# AutoFeatherPower3.net
KiCad netlist of a schematic drawn in EAGLE
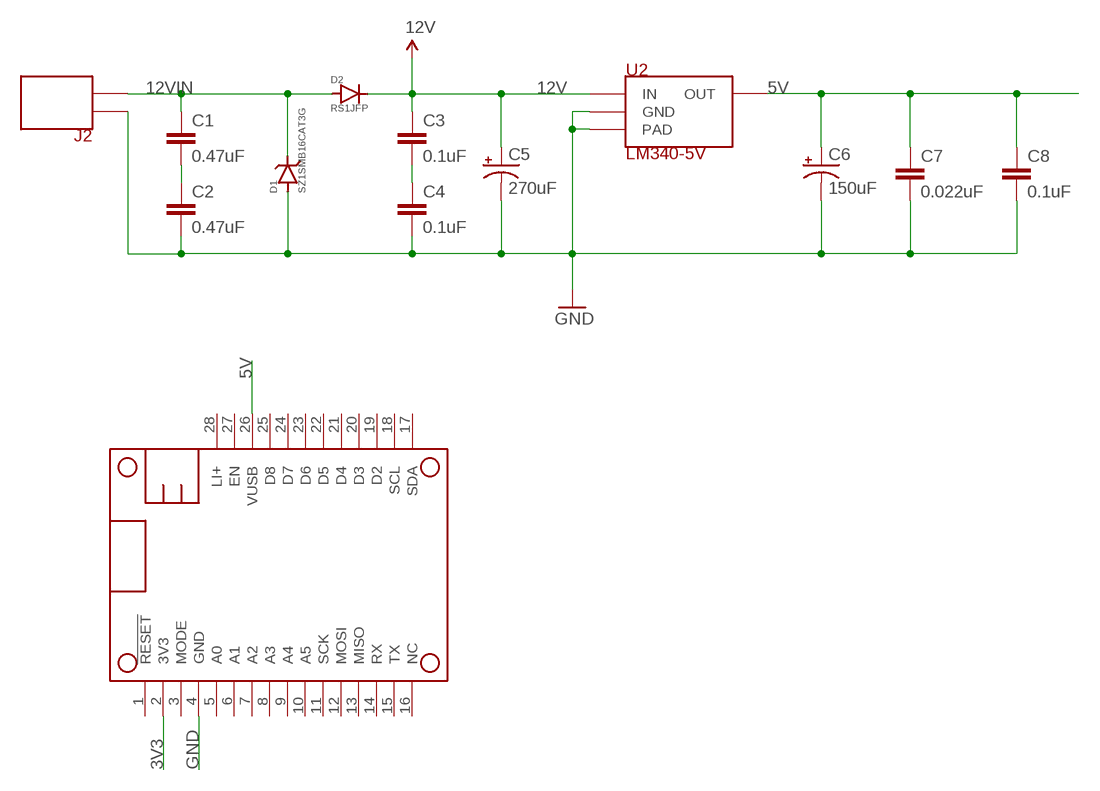
[diagram p0: schematic, sheet 1]

(export (version "E")
  (design (tool "Eeschema 10.0.6"))
  (components
    (comp (ref "C1")
      (value "0.47uF")
      (footprint "eagle-import:0805")
      (libsource (lib "eagle-import") (part "CAP-0.47UF-0805"))
    )
    (comp (ref "C2")
      (value "0.47uF")
      (footprint "eagle-import:0805")
      (libsource (lib "eagle-import") (part "CAP-0.47UF-0805"))
    )
    (comp (ref "C3")
      (value "0.1uF")
      (footprint "eagle-import:0603-CAP")
      (libsource (lib "eagle-import") (part "CAP-0.1UF-0603"))
    )
    (comp (ref "C4")
      (value "0.1uF")
      (footprint "eagle-import:0603-CAP")
      (libsource (lib "eagle-import") (part "CAP-0.1UF-0603"))
    )
    (comp (ref "C5")
      (value "270uF")
      (footprint "eagle-import:CAP-PANASONIC-FKS-V-F")
      (libsource (lib "eagle-import") (part "CAP-270UF-35V-SMD"))
    )
    (comp (ref "C6")
      (value "150uF")
      (footprint "eagle-import:CAP-PANASONIC-FKS-V-D")
      (libsource (lib "eagle-import") (part "CAP-150UF-10V-SMD"))
    )
    (comp (ref "C7")
      (value "0.022uF")
      (footprint "eagle-import:0603-CAP")
      (libsource (lib "eagle-import") (part "CAP-0.022UF-0603"))
    )
    (comp (ref "C8")
      (value "0.1uF")
      (footprint "eagle-import:0603-CAP")
      (libsource (lib "eagle-import") (part "CAP-0.1UF-0603"))
    )
    (comp (ref "D1")
      (value "SZ1SMB16CAT3G")
      (footprint "eagle-import:SZ1SMB")
      (libsource (lib "eagle-import") (part "DIODE-TVS-SZ1SMB"))
    )
    (comp (ref "D2")
      (value "RS1JFP")
      (footprint "eagle-import:SOD-123HE-ON")
      (libsource (lib "eagle-import") (part "DIODE-RS1JFP"))
    )
    (comp (ref "J2")
      (value "TERMBLOCK-2X3.5MM")
      (footprint "eagle-import:TERMBLOCK-2X3.5MM")
      (libsource (lib "eagle-import") (part "TERMBLOCK-2X3.5MM"))
    )
    (comp (ref "MS1")
      (value "FEATHERWING_NODIM")
      (footprint "eagle-import:FEATHERWING_NODIM")
      (libsource (lib "eagle-import") (part "FEATHERWING_NODIM"))
    )
    (comp (ref "U2")
      (value "LM340-5V")
      (footprint "eagle-import:TO-263-3-TI")
      (libsource (lib "eagle-import") (part "LM340"))
    )
  )
  (nets
    (net (code "1") (name "/3V3") (class "Default")
      (node (ref "MS1") (pin "2") (pinfunction "3V3_2") (pintype "power_in"))
    )
    (net (code "2") (name "/5V") (class "Default")
      (node (ref "C6") (pin "P+") (pinfunction "+_P+") (pintype "passive"))
      (node (ref "C7") (pin "1") (pinfunction "1_1") (pintype "passive"))
      (node (ref "C8") (pin "1") (pinfunction "1_1") (pintype "passive"))
      (node (ref "MS1") (pin "26") (pinfunction "VUSB_26") (pintype "power_in"))
      (node (ref "U2") (pin "3") (pinfunction "OUT_3") (pintype "power_in"))
    )
    (net (code "3") (name "/12VIN") (class "Default")
      (node (ref "C1") (pin "1") (pinfunction "1_1") (pintype "passive"))
      (node (ref "D1") (pin "C") (pinfunction "CATHODE_C") (pintype "bidirectional"))
      (node (ref "D2") (pin "2") (pinfunction "ANODE_2") (pintype "bidirectional"))
      (node (ref "J2") (pin "2") (pinfunction "2_2") (pintype "passive"))
    )
    (net (code "4") (name "/LI+") (class "Default")
      (node (ref "MS1") (pin "28") (pinfunction "LI+_28") (pintype "power_in"))
    )
    (net (code "5") (name "12V") (class "Default")
      (node (ref "C3") (pin "1") (pinfunction "1_1") (pintype "passive"))
      (node (ref "C5") (pin "P+") (pinfunction "+_P+") (pintype "passive"))
      (node (ref "D2") (pin "1") (pinfunction "CATHODE_1") (pintype "bidirectional"))
      (node (ref "U2") (pin "1") (pinfunction "IN_1") (pintype "power_in"))
    )
    (net (code "6") (name "GND") (class "Default")
      (node (ref "C2") (pin "2") (pinfunction "2_2") (pintype "passive"))
      (node (ref "C4") (pin "2") (pinfunction "2_2") (pintype "passive"))
      (node (ref "C5") (pin "P-") (pinfunction "-_P-") (pintype "passive"))
      (node (ref "C6") (pin "P-") (pinfunction "-_P-") (pintype "passive"))
      (node (ref "C7") (pin "2") (pinfunction "2_2") (pintype "passive"))
      (node (ref "C8") (pin "2") (pinfunction "2_2") (pintype "passive"))
      (node (ref "D1") (pin "A") (pinfunction "ANODE_A") (pintype "bidirectional"))
      (node (ref "J2") (pin "1") (pinfunction "1_1") (pintype "passive"))
      (node (ref "MS1") (pin "4") (pinfunction "GND_4") (pintype "power_in"))
      (node (ref "U2") (pin "2") (pinfunction "GND_2") (pintype "power_in"))
      (node (ref "U2") (pin "PAD") (pinfunction "PAD_PAD") (pintype "power_in"))
    )
    (net (code "7") (name "Net-(C1-Pad2)") (class "Default")
      (node (ref "C1") (pin "2") (pinfunction "2_2") (pintype "passive"))
      (node (ref "C2") (pin "1") (pinfunction "1_1") (pintype "passive"))
    )
    (net (code "8") (name "Net-(C3-Pad2)") (class "Default")
      (node (ref "C3") (pin "2") (pinfunction "2_2") (pintype "passive"))
      (node (ref "C4") (pin "1") (pinfunction "1_1") (pintype "passive"))
    )
    (net (code "9") (name "unconnected-(MS1-A0-Pad5)") (class "Default")
      (node (ref "MS1") (pin "5") (pinfunction "A0_5") (pintype "bidirectional"))
    )
    (net (code "10") (name "unconnected-(MS1-A1-Pad6)") (class "Default")
      (node (ref "MS1") (pin "6") (pinfunction "A1_6") (pintype "bidirectional"))
    )
    (net (code "11") (name "unconnected-(MS1-A2-Pad7)") (class "Default")
      (node (ref "MS1") (pin "7") (pinfunction "A2_7") (pintype "bidirectional"))
    )
    (net (code "12") (name "unconnected-(MS1-A3-Pad8)") (class "Default")
      (node (ref "MS1") (pin "8") (pinfunction "A3_8") (pintype "bidirectional"))
    )
    (net (code "13") (name "unconnected-(MS1-A4-Pad9)") (class "Default")
      (node (ref "MS1") (pin "9") (pinfunction "A4_9") (pintype "bidirectional"))
    )
    (net (code "14") (name "unconnected-(MS1-A5-Pad10)") (class "Default")
      (node (ref "MS1") (pin "10") (pinfunction "A5_10") (pintype "bidirectional"))
    )
    (net (code "15") (name "unconnected-(MS1-D2-Pad19)") (class "Default")
      (node (ref "MS1") (pin "19") (pinfunction "D2_19") (pintype "bidirectional"))
    )
    (net (code "16") (name "unconnected-(MS1-D3-Pad20)") (class "Default")
      (node (ref "MS1") (pin "20") (pinfunction "D3_20") (pintype "bidirectional"))
    )
    (net (code "17") (name "unconnected-(MS1-D4-Pad21)") (class "Default")
      (node (ref "MS1") (pin "21") (pinfunction "D4_21") (pintype "bidirectional"))
    )
    (net (code "18") (name "unconnected-(MS1-D5-Pad22)") (class "Default")
      (node (ref "MS1") (pin "22") (pinfunction "D5_22") (pintype "bidirectional"))
    )
    (net (code "19") (name "unconnected-(MS1-D6-Pad23)") (class "Default")
      (node (ref "MS1") (pin "23") (pinfunction "D6_23") (pintype "bidirectional"))
    )
    (net (code "20") (name "unconnected-(MS1-D7-Pad24)") (class "Default")
      (node (ref "MS1") (pin "24") (pinfunction "D7_24") (pintype "bidirectional"))
    )
    (net (code "21") (name "unconnected-(MS1-D8-Pad25)") (class "Default")
      (node (ref "MS1") (pin "25") (pinfunction "D8_25") (pintype "bidirectional"))
    )
    (net (code "22") (name "unconnected-(MS1-EN-Pad27)") (class "Default")
      (node (ref "MS1") (pin "27") (pinfunction "EN_27") (pintype "passive"))
    )
    (net (code "23") (name "unconnected-(MS1-MISO-Pad13)") (class "Default")
      (node (ref "MS1") (pin "13") (pinfunction "MISO_13") (pintype "bidirectional"))
    )
    (net (code "24") (name "unconnected-(MS1-MODE-Pad3)") (class "Default")
      (node (ref "MS1") (pin "3") (pinfunction "MODE_3") (pintype "passive"))
    )
    (net (code "25") (name "unconnected-(MS1-MOSI-Pad12)") (class "Default")
      (node (ref "MS1") (pin "12") (pinfunction "MOSI_12") (pintype "bidirectional"))
    )
    (net (code "26") (name "unconnected-(MS1-NC-Pad16)") (class "Default")
      (node (ref "MS1") (pin "16") (pinfunction "NC_16") (pintype "passive"))
    )
    (net (code "27") (name "unconnected-(MS1-RX-Pad14)") (class "Default")
      (node (ref "MS1") (pin "14") (pinfunction "RX_14") (pintype "bidirectional"))
    )
    (net (code "28") (name "unconnected-(MS1-SCK-Pad11)") (class "Default")
      (node (ref "MS1") (pin "11") (pinfunction "SCK_11") (pintype "bidirectional"))
    )
    (net (code "29") (name "unconnected-(MS1-SCL-Pad18)") (class "Default")
      (node (ref "MS1") (pin "18") (pinfunction "SCL_18") (pintype "bidirectional"))
    )
    (net (code "30") (name "unconnected-(MS1-SDA-Pad17)") (class "Default")
      (node (ref "MS1") (pin "17") (pinfunction "SDA_17") (pintype "bidirectional"))
    )
    (net (code "31") (name "unconnected-(MS1-TX-Pad15)") (class "Default")
      (node (ref "MS1") (pin "15") (pinfunction "TX_15") (pintype "bidirectional"))
    )
    (net (code "32") (name "unconnected-(MS1-~{RESET}-Pad1)") (class "Default")
      (node (ref "MS1") (pin "1") (pinfunction "~{RESET}_1") (pintype "input"))
    )
  )
)
